# ledsayici.net
KiCad netlist of a schematic drawn in Altium Designer
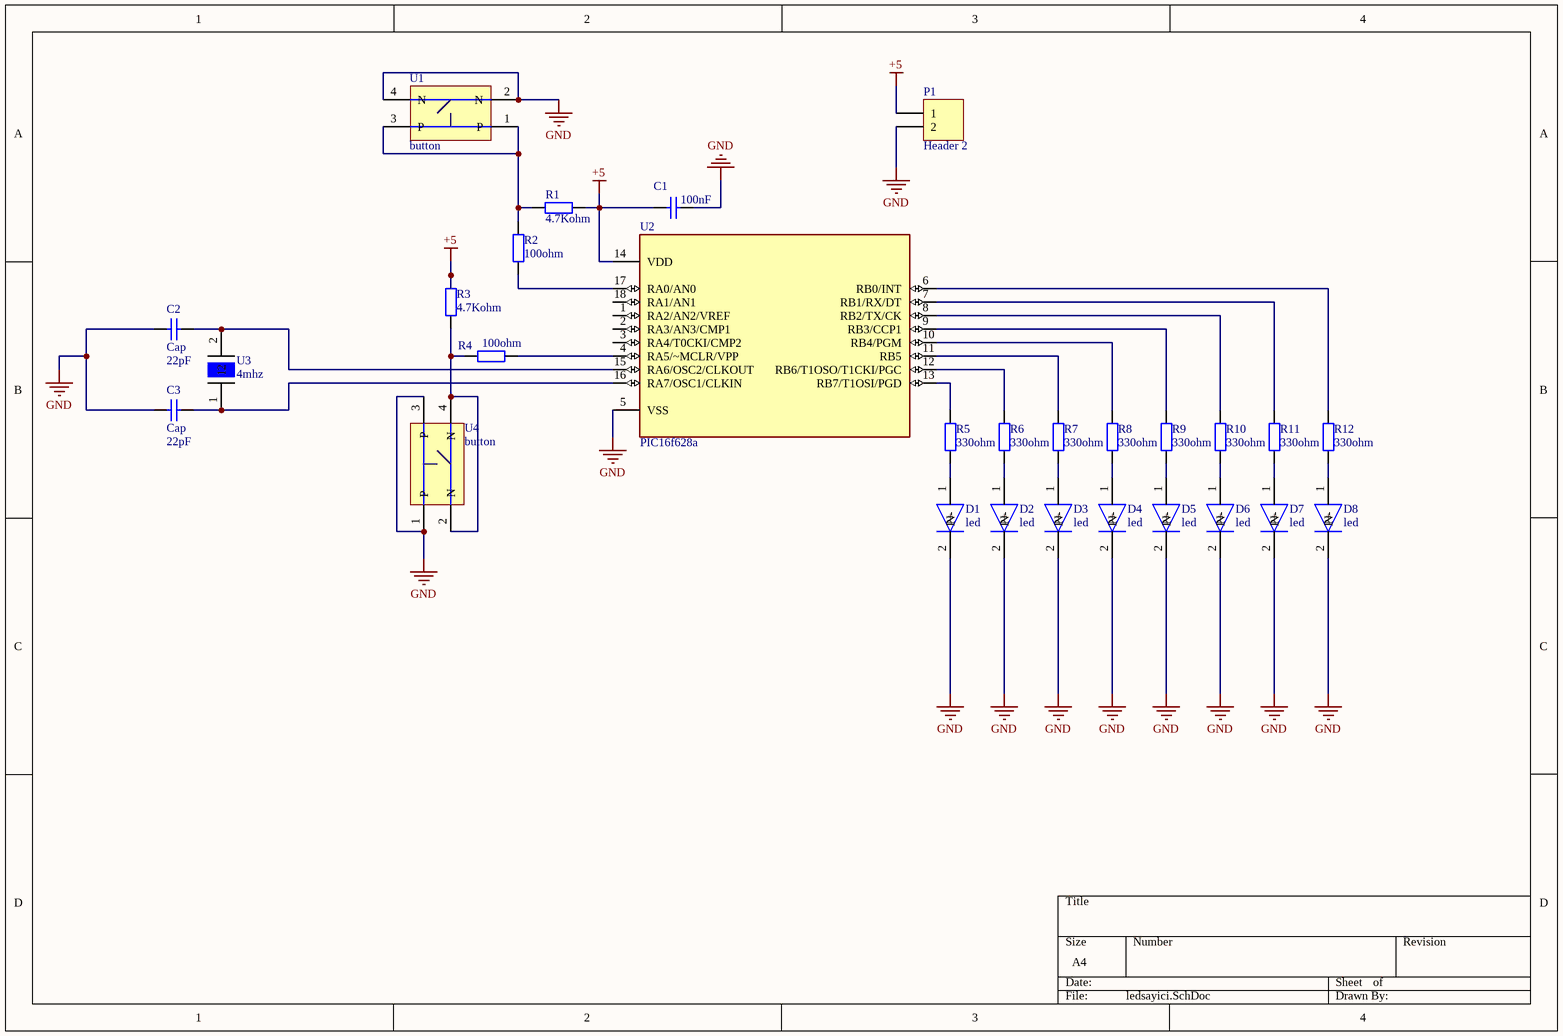
[diagram p0: ledsayici.SchDoc]

(export (version "E")
  (design (tool "Eeschema 10.0.6"))
  (components
    (comp (ref "C1")
      (value "100nF")
      (footprint "RAD-0.3")
      (description "Capacitor")
      (fields (field (name "Comment") "Cap") (field (name "PUBLISHER") "Altium Limited"))
      (libsource (lib "Miscellaneous Devices") (part "Cap"))
    )
    (comp (ref "C2")
      (value "Cap")
      (footprint "RAD-0.3")
      (description "Capacitor")
      (fields (field (name "ALTIUM_VALUE") "22pF") (field (name "PUBLISHER") "Altium Limited"))
      (libsource (lib "Miscellaneous Devices") (part "Cap"))
    )
    (comp (ref "C3")
      (value "Cap")
      (footprint "RAD-0.3")
      (description "Capacitor")
      (fields (field (name "ALTIUM_VALUE") "22pF") (field (name "PUBLISHER") "Altium Limited"))
      (libsource (lib "Miscellaneous Devices") (part "Cap"))
    )
    (comp (ref "D1") (value "led") (footprint "led") (libsource (lib "ledsayici") (part "led")))
    (comp (ref "D2") (value "led") (footprint "led") (libsource (lib "ledsayici") (part "led")))
    (comp (ref "D3") (value "led") (footprint "led") (libsource (lib "ledsayici") (part "led")))
    (comp (ref "D4") (value "led") (footprint "led") (libsource (lib "ledsayici") (part "led")))
    (comp (ref "D5") (value "led") (footprint "led") (libsource (lib "ledsayici") (part "led")))
    (comp (ref "D6") (value "led") (footprint "led") (libsource (lib "ledsayici") (part "led")))
    (comp (ref "D7") (value "led") (footprint "led") (libsource (lib "ledsayici") (part "led")))
    (comp (ref "D8") (value "led") (footprint "led") (libsource (lib "ledsayici") (part "led")))
    (comp (ref "P1")
      (value "Header 2")
      (footprint "HDR1X2")
      (description "Header, 2-Pin")
      (fields (field (name "PUBLISHER") "Altium Limited"))
      (libsource (lib "Miscellaneous Connectors") (part "Header 2"))
    )
    (comp (ref "R1")
      (value "4.7Kohm")
      (footprint "AXIAL-0.4")
      (description "Resistor")
      (fields (field (name "Comment") "Res2") (field (name "PUBLISHER") "Altium Limited"))
      (libsource (lib "") (part "Res2_2"))
    )
    (comp (ref "R2")
      (value "100ohm")
      (footprint "AXIAL-0.4")
      (description "Resistor")
      (fields (field (name "Comment") "Res2") (field (name "PUBLISHER") "Altium Limited"))
      (libsource (lib "Miscellaneous Devices") (part "Res2"))
    )
    (comp (ref "R3")
      (value "4.7Kohm")
      (footprint "AXIAL-0.4")
      (description "Resistor")
      (fields (field (name "Comment") "Res2") (field (name "PUBLISHER") "Altium Limited"))
      (libsource (lib "Miscellaneous Devices") (part "Res2"))
    )
    (comp (ref "R4")
      (value "100ohm")
      (footprint "AXIAL-0.4")
      (description "Resistor")
      (fields (field (name "Comment") "Res2") (field (name "PUBLISHER") "Altium Limited"))
      (libsource (lib "") (part "Res2_1"))
    )
    (comp (ref "R5")
      (value "330ohm")
      (footprint "AXIAL-0.4")
      (description "Resistor")
      (fields (field (name "Comment") "Res2") (field (name "PUBLISHER") "Altium Limited"))
      (libsource (lib "Miscellaneous Devices") (part "Res2"))
    )
    (comp (ref "R6")
      (value "330ohm")
      (footprint "AXIAL-0.4")
      (description "Resistor")
      (fields (field (name "Comment") "Res2") (field (name "PUBLISHER") "Altium Limited"))
      (libsource (lib "Miscellaneous Devices") (part "Res2"))
    )
    (comp (ref "R7")
      (value "330ohm")
      (footprint "AXIAL-0.4")
      (description "Resistor")
      (fields (field (name "Comment") "Res2") (field (name "PUBLISHER") "Altium Limited"))
      (libsource (lib "Miscellaneous Devices") (part "Res2"))
    )
    (comp (ref "R8")
      (value "330ohm")
      (footprint "AXIAL-0.4")
      (description "Resistor")
      (fields (field (name "Comment") "Res2") (field (name "PUBLISHER") "Altium Limited"))
      (libsource (lib "Miscellaneous Devices") (part "Res2"))
    )
    (comp (ref "R9")
      (value "330ohm")
      (footprint "AXIAL-0.4")
      (description "Resistor")
      (fields (field (name "Comment") "Res2") (field (name "PUBLISHER") "Altium Limited"))
      (libsource (lib "Miscellaneous Devices") (part "Res2"))
    )
    (comp (ref "R10")
      (value "330ohm")
      (footprint "AXIAL-0.4")
      (description "Resistor")
      (fields (field (name "Comment") "Res2") (field (name "PUBLISHER") "Altium Limited"))
      (libsource (lib "Miscellaneous Devices") (part "Res2"))
    )
    (comp (ref "R11")
      (value "330ohm")
      (footprint "AXIAL-0.4")
      (description "Resistor")
      (fields (field (name "Comment") "Res2") (field (name "PUBLISHER") "Altium Limited"))
      (libsource (lib "Miscellaneous Devices") (part "Res2"))
    )
    (comp (ref "R12")
      (value "330ohm")
      (footprint "AXIAL-0.4")
      (description "Resistor")
      (fields (field (name "Comment") "Res2") (field (name "PUBLISHER") "Altium Limited"))
      (libsource (lib "Miscellaneous Devices") (part "Res2"))
    )
    (comp (ref "U1") (value "button") (footprint "buton") (libsource (lib "") (part "button_1")))
    (comp (ref "U2")
      (value "PIC16f628a")
      (footprint "PCBComponent_1")
      (libsource (lib "ledsayici") (part "PIC16f628a"))
    )
    (comp (ref "U3") (value "4mhz") (footprint "4mhz") (libsource (lib "ledsayici") (part "4mhz")))
    (comp (ref "U4") (value "button") (footprint "buton") (libsource (lib "ledsayici") (part "button")))
  )
  (nets
    (net (code "1") (name "+5") (class "Default")
      (node (ref "C1") (pin "1") (pinfunction "1_1") (pintype "passive"))
      (node (ref "P1") (pin "1") (pinfunction "1_1") (pintype "passive"))
      (node (ref "R1") (pin "1") (pinfunction "1_1") (pintype "passive"))
      (node (ref "R3") (pin "2") (pinfunction "2_2") (pintype "passive"))
      (node (ref "U2") (pin "14") (pinfunction "VDD_14") (pintype "power_in"))
    )
    (net (code "2") (name "GND") (class "Default")
      (node (ref "C1") (pin "2") (pinfunction "2_2") (pintype "passive"))
      (node (ref "C2") (pin "1") (pinfunction "1_1") (pintype "passive"))
      (node (ref "C3") (pin "1") (pinfunction "1_1") (pintype "passive"))
      (node (ref "D1") (pin "2") (pinfunction "N-_2") (pintype "passive"))
      (node (ref "D2") (pin "2") (pinfunction "N-_2") (pintype "passive"))
      (node (ref "D3") (pin "2") (pinfunction "N-_2") (pintype "passive"))
      (node (ref "D4") (pin "2") (pinfunction "N-_2") (pintype "passive"))
      (node (ref "D5") (pin "2") (pinfunction "N-_2") (pintype "passive"))
      (node (ref "D6") (pin "2") (pinfunction "N-_2") (pintype "passive"))
      (node (ref "D7") (pin "2") (pinfunction "N-_2") (pintype "passive"))
      (node (ref "D8") (pin "2") (pinfunction "N-_2") (pintype "passive"))
      (node (ref "P1") (pin "2") (pinfunction "2_2") (pintype "passive"))
      (node (ref "U1") (pin "2") (pinfunction "N_2") (pintype "passive"))
      (node (ref "U1") (pin "4") (pinfunction "N_4") (pintype "passive"))
      (node (ref "U2") (pin "5") (pinfunction "VSS_5") (pintype "power_in"))
      (node (ref "U4") (pin "1") (pinfunction "P_1") (pintype "passive"))
      (node (ref "U4") (pin "3") (pinfunction "P_3") (pintype "passive"))
    )
    (net (code "3") (name "Net-(D1-P+)") (class "Default")
      (node (ref "D1") (pin "1") (pinfunction "P+_1") (pintype "passive"))
      (node (ref "R5") (pin "1") (pinfunction "1_1") (pintype "passive"))
    )
    (net (code "4") (name "Net-(D2-P+)") (class "Default")
      (node (ref "D2") (pin "1") (pinfunction "P+_1") (pintype "passive"))
      (node (ref "R6") (pin "1") (pinfunction "1_1") (pintype "passive"))
    )
    (net (code "5") (name "Net-(D3-P+)") (class "Default")
      (node (ref "D3") (pin "1") (pinfunction "P+_1") (pintype "passive"))
      (node (ref "R7") (pin "1") (pinfunction "1_1") (pintype "passive"))
    )
    (net (code "6") (name "Net-(D4-P+)") (class "Default")
      (node (ref "D4") (pin "1") (pinfunction "P+_1") (pintype "passive"))
      (node (ref "R8") (pin "1") (pinfunction "1_1") (pintype "passive"))
    )
    (net (code "7") (name "Net-(D5-P+)") (class "Default")
      (node (ref "D5") (pin "1") (pinfunction "P+_1") (pintype "passive"))
      (node (ref "R9") (pin "1") (pinfunction "1_1") (pintype "passive"))
    )
    (net (code "8") (name "Net-(D6-P+)") (class "Default")
      (node (ref "D6") (pin "1") (pinfunction "P+_1") (pintype "passive"))
      (node (ref "R10") (pin "1") (pinfunction "1_1") (pintype "passive"))
    )
    (net (code "9") (name "Net-(D7-P+)") (class "Default")
      (node (ref "D7") (pin "1") (pinfunction "P+_1") (pintype "passive"))
      (node (ref "R11") (pin "1") (pinfunction "1_1") (pintype "passive"))
    )
    (net (code "10") (name "Net-(D8-P+)") (class "Default")
      (node (ref "D8") (pin "1") (pinfunction "P+_1") (pintype "passive"))
      (node (ref "R12") (pin "1") (pinfunction "1_1") (pintype "passive"))
    )
    (net (code "11") (name "Net-(R1-Pad2)") (class "Default")
      (node (ref "R1") (pin "2") (pinfunction "2_2") (pintype "passive"))
      (node (ref "R2") (pin "2") (pinfunction "2_2") (pintype "passive"))
      (node (ref "U1") (pin "1") (pinfunction "P_1") (pintype "passive"))
      (node (ref "U1") (pin "3") (pinfunction "P_3") (pintype "passive"))
    )
    (net (code "12") (name "Net-(R3-Pad1)") (class "Default")
      (node (ref "R3") (pin "1") (pinfunction "1_1") (pintype "passive"))
      (node (ref "R4") (pin "1") (pinfunction "1_1") (pintype "passive"))
      (node (ref "U4") (pin "2") (pinfunction "N_2") (pintype "passive"))
      (node (ref "U4") (pin "4") (pinfunction "N_4") (pintype "passive"))
    )
    (net (code "13") (name "Net-(U2-RA0{slash}AN0)") (class "Default")
      (node (ref "R2") (pin "1") (pinfunction "1_1") (pintype "passive"))
      (node (ref "U2") (pin "17") (pinfunction "RA0/AN0_17") (pintype "bidirectional"))
    )
    (net (code "14") (name "Net-(U2-RA5{slash}~MCLR{slash}VPP)") (class "Default")
      (node (ref "R4") (pin "2") (pinfunction "2_2") (pintype "passive"))
      (node (ref "U2") (pin "4") (pinfunction "RA5/~MCLR/VPP_4") (pintype "bidirectional"))
    )
    (net (code "15") (name "Net-(U2-RA6{slash}OSC2{slash}CLKOUT)") (class "Default")
      (node (ref "C2") (pin "2") (pinfunction "2_2") (pintype "passive"))
      (node (ref "U2") (pin "15") (pinfunction "RA6/OSC2/CLKOUT_15") (pintype "bidirectional"))
      (node (ref "U3") (pin "2") (pinfunction "2_2") (pintype "passive"))
    )
    (net (code "16") (name "Net-(U2-RA7{slash}OSC1{slash}CLKIN)") (class "Default")
      (node (ref "C3") (pin "2") (pinfunction "2_2") (pintype "passive"))
      (node (ref "U2") (pin "16") (pinfunction "RA7/OSC1/CLKIN_16") (pintype "bidirectional"))
      (node (ref "U3") (pin "1") (pinfunction "1_1") (pintype "passive"))
    )
    (net (code "17") (name "Net-(U2-RB0{slash}INT)") (class "Default")
      (node (ref "R12") (pin "2") (pinfunction "2_2") (pintype "passive"))
      (node (ref "U2") (pin "6") (pinfunction "RB0/INT_6") (pintype "bidirectional"))
    )
    (net (code "18") (name "Net-(U2-RB1{slash}RX{slash}DT)") (class "Default")
      (node (ref "R11") (pin "2") (pinfunction "2_2") (pintype "passive"))
      (node (ref "U2") (pin "7") (pinfunction "RB1/RX/DT_7") (pintype "bidirectional"))
    )
    (net (code "19") (name "Net-(U2-RB2{slash}TX{slash}CK)") (class "Default")
      (node (ref "R10") (pin "2") (pinfunction "2_2") (pintype "passive"))
      (node (ref "U2") (pin "8") (pinfunction "RB2/TX/CK_8") (pintype "bidirectional"))
    )
    (net (code "20") (name "Net-(U2-RB3{slash}CCP1)") (class "Default")
      (node (ref "R9") (pin "2") (pinfunction "2_2") (pintype "passive"))
      (node (ref "U2") (pin "9") (pinfunction "RB3/CCP1_9") (pintype "bidirectional"))
    )
    (net (code "21") (name "Net-(U2-RB4{slash}PGM)") (class "Default")
      (node (ref "R8") (pin "2") (pinfunction "2_2") (pintype "passive"))
      (node (ref "U2") (pin "10") (pinfunction "RB4/PGM_10") (pintype "bidirectional"))
    )
    (net (code "22") (name "Net-(U2-RB5)") (class "Default")
      (node (ref "R7") (pin "2") (pinfunction "2_2") (pintype "passive"))
      (node (ref "U2") (pin "11") (pinfunction "RB5_11") (pintype "bidirectional"))
    )
    (net (code "23") (name "Net-(U2-RB6{slash}T1OSO{slash}T1CKI{slash}PGC)") (class "Default")
      (node (ref "R6") (pin "2") (pinfunction "2_2") (pintype "passive"))
      (node (ref "U2") (pin "12") (pinfunction "RB6/T1OSO/T1CKI/PGC_12") (pintype "bidirectional"))
    )
    (net (code "24") (name "Net-(U2-RB7{slash}T1OSI{slash}PGD)") (class "Default")
      (node (ref "R5") (pin "2") (pinfunction "2_2") (pintype "passive"))
      (node (ref "U2") (pin "13") (pinfunction "RB7/T1OSI/PGD_13") (pintype "bidirectional"))
    )
    (net (code "25") (name "unconnected-(U2-RA1{slash}AN1-Pad18)") (class "Default")
      (node (ref "U2") (pin "18") (pinfunction "RA1/AN1_18") (pintype "bidirectional"))
    )
    (net (code "26") (name "unconnected-(U2-RA2{slash}AN2{slash}VREF-Pad1)") (class "Default")
      (node (ref "U2") (pin "1") (pinfunction "RA2/AN2/VREF_1") (pintype "bidirectional"))
    )
    (net (code "27") (name "unconnected-(U2-RA3{slash}AN3{slash}CMP1-Pad2)") (class "Default")
      (node (ref "U2") (pin "2") (pinfunction "RA3/AN3/CMP1_2") (pintype "bidirectional"))
    )
    (net (code "28") (name "unconnected-(U2-RA4{slash}T0CKI{slash}CMP2-Pad3)") (class "Default")
      (node (ref "U2") (pin "3") (pinfunction "RA4/T0CKI/CMP2_3") (pintype "bidirectional"))
    )
  )
)
